# SimGEKI2_Core.net
KiCad netlist of a schematic drawn in EasyEDA Pro
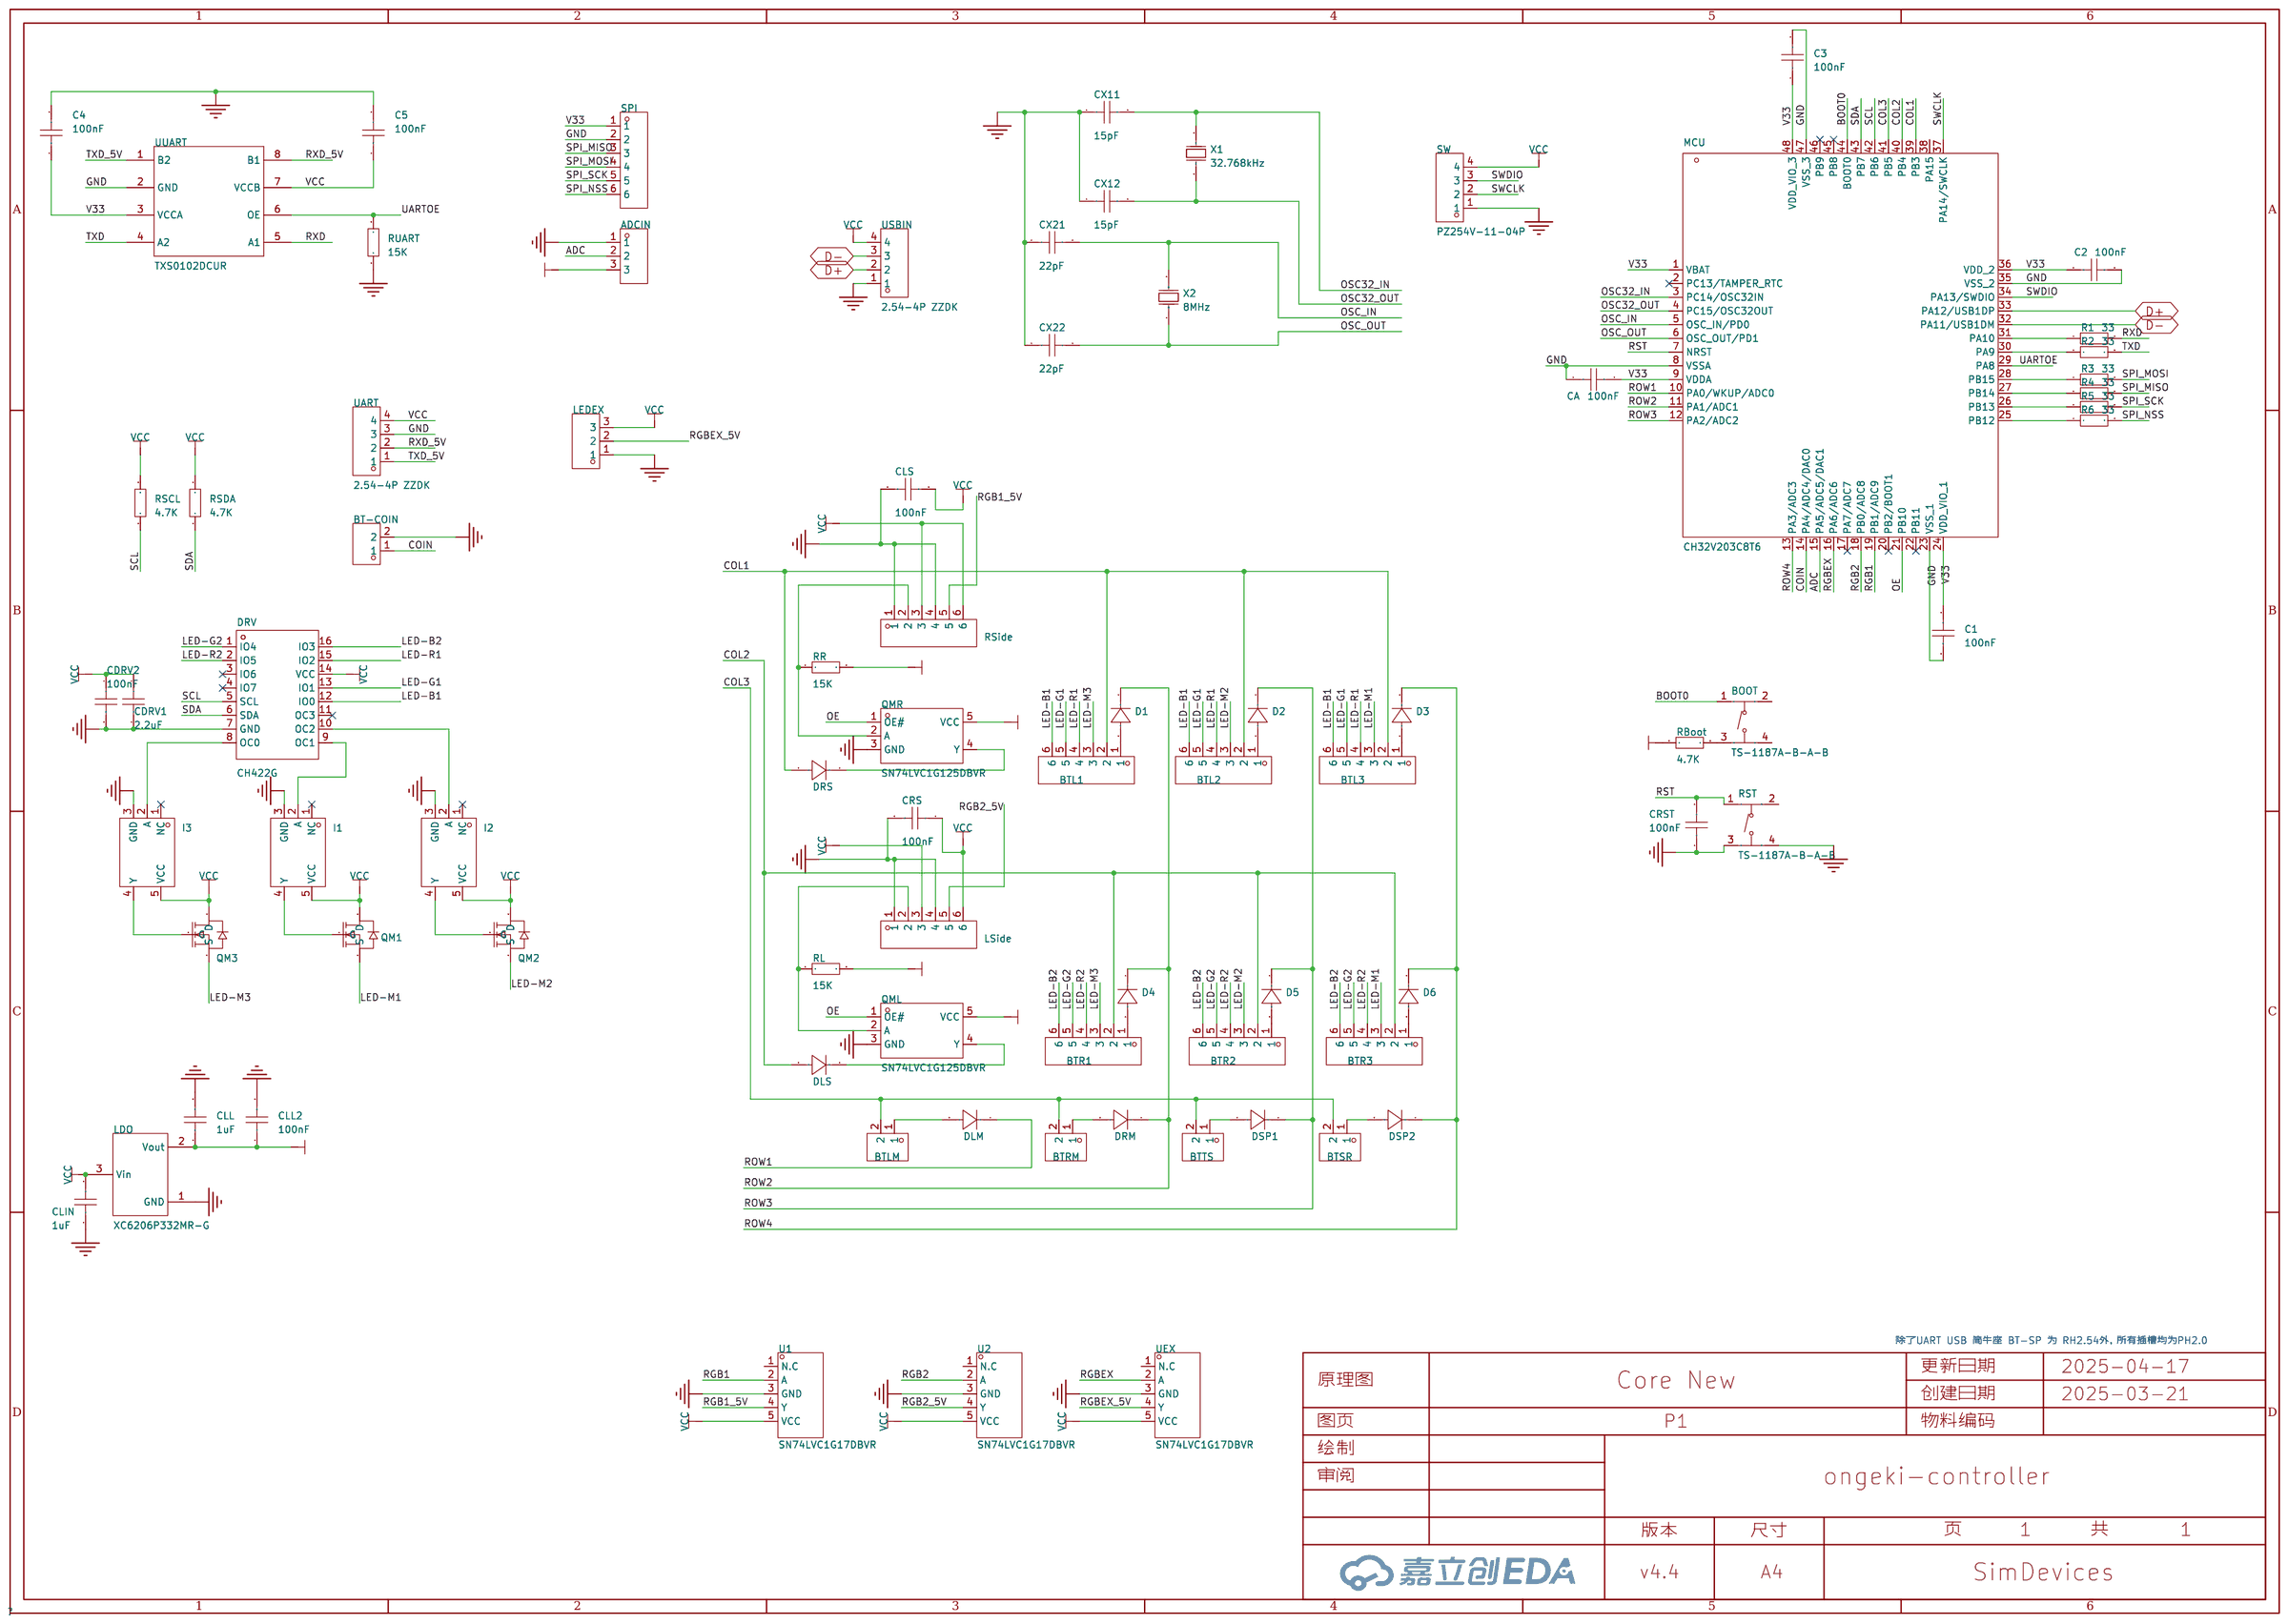
[diagram p0: schematic sheet]

(export (version "E")
  (design (tool "Eeschema 10.0.6"))
  (components
    (comp (ref "ADCIN")
      (value "HDGC2001WV-3P")
      (footprint "easyedapro:CONN-TH_3P-P2.00_HDGC2001WV-3P")
      (fields (field (name "Manufacturer") "HDGC(华德共创)"))
      (libsource (lib "easyedapro") (part "HDGC2001WV-3P"))
    )
    (comp (ref "BOOT")
      (value "TS-1187A-B-A-B")
      (footprint "easyedapro:SW-SMD_4P-L5.1-W5.1-P3.70-LS6.5-TL_H1.5")
      (fields (field (name "Manufacturer") "XKB Connectivity(中国星坤)"))
      (libsource (lib "easyedapro") (part "TS-1187A-B-A-B"))
    )
    (comp (ref "BT-COIN")
      (value "ZX-XH2.54-2PZZ")
      (fields (field (name "Manufacturer") "Megastar(兆星)"))
      (libsource (lib "easyedapro") (part "HDGC2001WV-2P"))
    )
    (comp (ref "BTL1")
      (value "HDGC2001WV-6P")
      (footprint "easyedapro:CONN-TH_6P-P2.00_HDGC2001WV-6P")
      (fields (field (name "Manufacturer") "HDGC(华德共创)"))
      (libsource (lib "easyedapro") (part "HDGC2001WV-6P"))
    )
    (comp (ref "BTL2")
      (value "HDGC2001WV-6P")
      (footprint "easyedapro:CONN-TH_6P-P2.00_HDGC2001WV-6P")
      (fields (field (name "Manufacturer") "HDGC(华德共创)"))
      (libsource (lib "easyedapro") (part "HDGC2001WV-6P"))
    )
    (comp (ref "BTL3")
      (value "HDGC2001WV-6P")
      (footprint "easyedapro:CONN-TH_6P-P2.00_HDGC2001WV-6P")
      (fields (field (name "Manufacturer") "HDGC(华德共创)"))
      (libsource (lib "easyedapro") (part "HDGC2001WV-6P"))
    )
    (comp (ref "BTLM")
      (value "ZX-XH2.54-2PZZ")
      (fields (field (name "Manufacturer") "Megastar(兆星)"))
      (libsource (lib "easyedapro") (part "HDGC2001WV-2P"))
    )
    (comp (ref "BTR1")
      (value "HDGC2001WV-6P")
      (footprint "easyedapro:CONN-TH_6P-P2.00_HDGC2001WV-6P")
      (fields (field (name "Manufacturer") "HDGC(华德共创)"))
      (libsource (lib "easyedapro") (part "HDGC2001WV-6P"))
    )
    (comp (ref "BTR2")
      (value "HDGC2001WV-6P")
      (footprint "easyedapro:CONN-TH_6P-P2.00_HDGC2001WV-6P")
      (fields (field (name "Manufacturer") "HDGC(华德共创)"))
      (libsource (lib "easyedapro") (part "HDGC2001WV-6P"))
    )
    (comp (ref "BTR3")
      (value "HDGC2001WV-6P")
      (footprint "easyedapro:CONN-TH_6P-P2.00_HDGC2001WV-6P")
      (fields (field (name "Manufacturer") "HDGC(华德共创)"))
      (libsource (lib "easyedapro") (part "HDGC2001WV-6P"))
    )
    (comp (ref "BTRM")
      (value "ZX-XH2.54-2PZZ")
      (fields (field (name "Manufacturer") "Megastar(兆星)"))
      (libsource (lib "easyedapro") (part "HDGC2001WV-2P"))
    )
    (comp (ref "BTSR")
      (value "ZX-XH2.54-2PZZ")
      (fields (field (name "Manufacturer") "Megastar(兆星)"))
      (libsource (lib "easyedapro") (part "HDGC2001WV-2P"))
    )
    (comp (ref "BTTS")
      (value "ZX-XH2.54-2PZZ")
      (fields (field (name "Manufacturer") "Megastar(兆星)"))
      (libsource (lib "easyedapro") (part "HDGC2001WV-2P"))
    )
    (comp (ref "C1")
      (value "100nF")
      (footprint "easyedapro:C0603")
      (libsource (lib "easyedapro") (part "CapAcitance"))
    )
    (comp (ref "C2")
      (value "100nF")
      (footprint "easyedapro:C0603")
      (libsource (lib "easyedapro") (part "CapAcitance"))
    )
    (comp (ref "C3")
      (value "100nF")
      (footprint "easyedapro:C0603")
      (libsource (lib "easyedapro") (part "CapAcitance"))
    )
    (comp (ref "C4")
      (value "100nF")
      (footprint "easyedapro:C0603")
      (libsource (lib "easyedapro") (part "CapAcitance"))
    )
    (comp (ref "C5")
      (value "100nF")
      (footprint "easyedapro:C0603")
      (libsource (lib "easyedapro") (part "CapAcitance"))
    )
    (comp (ref "CA")
      (value "100nF")
      (footprint "easyedapro:C0603")
      (libsource (lib "easyedapro") (part "CapAcitance"))
    )
    (comp (ref "CDRV1")
      (value "2.2uF")
      (footprint "easyedapro:C0603")
      (libsource (lib "easyedapro") (part "CapAcitance"))
    )
    (comp (ref "CDRV2")
      (value "100nF")
      (footprint "easyedapro:C0603")
      (libsource (lib "easyedapro") (part "CapAcitance"))
    )
    (comp (ref "CLIN")
      (value "1uF")
      (footprint "easyedapro:C0603")
      (libsource (lib "easyedapro") (part "CapAcitance"))
    )
    (comp (ref "CLL")
      (value "1uF")
      (footprint "easyedapro:C0603")
      (libsource (lib "easyedapro") (part "CapAcitance"))
    )
    (comp (ref "CLL2")
      (value "100nF")
      (footprint "easyedapro:C0603")
      (libsource (lib "easyedapro") (part "CapAcitance"))
    )
    (comp (ref "CLS")
      (value "100nF")
      (footprint "easyedapro:C0603")
      (libsource (lib "easyedapro") (part "CapAcitance"))
    )
    (comp (ref "CRS")
      (value "100nF")
      (footprint "easyedapro:C0603")
      (libsource (lib "easyedapro") (part "CapAcitance"))
    )
    (comp (ref "CRST")
      (value "100nF")
      (footprint "easyedapro:C0603")
      (libsource (lib "easyedapro") (part "CapAcitance"))
    )
    (comp (ref "CX11")
      (value "15pF")
      (footprint "easyedapro:C0603")
      (libsource (lib "easyedapro") (part "CapAcitance"))
    )
    (comp (ref "CX12")
      (value "15pF")
      (footprint "easyedapro:C0603")
      (libsource (lib "easyedapro") (part "CapAcitance"))
    )
    (comp (ref "CX21")
      (value "22pF")
      (footprint "easyedapro:C0603")
      (libsource (lib "easyedapro") (part "CapAcitance"))
    )
    (comp (ref "CX22")
      (value "22pF")
      (footprint "easyedapro:C0603")
      (libsource (lib "easyedapro") (part "CapAcitance"))
    )
    (comp (ref "D1")
      (value "1N4148W")
      (fields (field (name "Manufacturer") "ST(先科)"))
      (libsource (lib "easyedapro") (part "1N4007_C9900004759"))
    )
    (comp (ref "D2")
      (value "1N4148W")
      (fields (field (name "Manufacturer") "ST(先科)"))
      (libsource (lib "easyedapro") (part "1N4007_C9900004759"))
    )
    (comp (ref "D3")
      (value "1N4148W")
      (fields (field (name "Manufacturer") "ST(先科)"))
      (libsource (lib "easyedapro") (part "1N4007_C9900004759"))
    )
    (comp (ref "D4")
      (value "1N4148W")
      (fields (field (name "Manufacturer") "ST(先科)"))
      (libsource (lib "easyedapro") (part "1N4007_C9900004759"))
    )
    (comp (ref "D5")
      (value "1N4148W")
      (fields (field (name "Manufacturer") "ST(先科)"))
      (libsource (lib "easyedapro") (part "1N4007_C9900004759"))
    )
    (comp (ref "D6")
      (value "1N4148W")
      (fields (field (name "Manufacturer") "ST(先科)"))
      (libsource (lib "easyedapro") (part "1N4007_C9900004759"))
    )
    (comp (ref "DLM")
      (value "1N4148W")
      (fields (field (name "Manufacturer") "ST(先科)"))
      (libsource (lib "easyedapro") (part "1N4007_C9900004759"))
    )
    (comp (ref "DLS")
      (value "1N4148W")
      (fields (field (name "Manufacturer") "ST(先科)"))
      (libsource (lib "easyedapro") (part "1N4007_C9900004759"))
    )
    (comp (ref "DRM")
      (value "1N4148W")
      (fields (field (name "Manufacturer") "ST(先科)"))
      (libsource (lib "easyedapro") (part "1N4007_C9900004759"))
    )
    (comp (ref "DRS")
      (value "1N4148W")
      (fields (field (name "Manufacturer") "ST(先科)"))
      (libsource (lib "easyedapro") (part "1N4007_C9900004759"))
    )
    (comp (ref "DRV")
      (value "CH422G")
      (footprint "easyedapro:SOP-16_L10.0-W3.9-P1.27-LS6.0-BL")
      (description "接口:I2C；SPI;I/O数量:8;时钟频率:1MHz;")
      (fields (field (name "Manufacturer") "WCH(南京沁恒)"))
      (libsource (lib "easyedapro") (part "CH422G"))
    )
    (comp (ref "DSP1")
      (value "1N4148W")
      (fields (field (name "Manufacturer") "ST(先科)"))
      (libsource (lib "easyedapro") (part "1N4007_C9900004759"))
    )
    (comp (ref "DSP2")
      (value "1N4148W")
      (fields (field (name "Manufacturer") "ST(先科)"))
      (libsource (lib "easyedapro") (part "1N4007_C9900004759"))
    )
    (comp (ref "I1")
      (value "SN74LVC1G14DBVR")
      (footprint "easyedapro:SOT-23-5_L3.0-W1.7-P0.95-LS2.8-BR")
      (description "逻辑电路的归属系列:-;逻辑类型:-;电路/元件数:-;输入数/每元件位数:-;电源电压:-;静态电流（最大值）:-;")
      (fields (field (name "Manufacturer") "UMW(广东友台半导体)"))
      (libsource (lib "easyedapro") (part "SN74LVC1G14DBVR_C434069"))
    )
    (comp (ref "I2")
      (value "SN74LVC1G14DBVR")
      (footprint "easyedapro:SOT-23-5_L3.0-W1.7-P0.95-LS2.8-BR")
      (description "逻辑电路的归属系列:-;逻辑类型:-;电路/元件数:-;输入数/每元件位数:-;电源电压:-;静态电流（最大值）:-;")
      (fields (field (name "Manufacturer") "UMW(广东友台半导体)"))
      (libsource (lib "easyedapro") (part "SN74LVC1G14DBVR_C434069"))
    )
    (comp (ref "I3")
      (value "SN74LVC1G14DBVR")
      (footprint "easyedapro:SOT-23-5_L3.0-W1.7-P0.95-LS2.8-BR")
      (description "逻辑电路的归属系列:-;逻辑类型:-;电路/元件数:-;输入数/每元件位数:-;电源电压:-;静态电流（最大值）:-;")
      (fields (field (name "Manufacturer") "UMW(广东友台半导体)"))
      (libsource (lib "easyedapro") (part "SN74LVC1G14DBVR_C434069"))
    )
    (comp (ref "LDO")
      (value "XC6206P332MR-G")
      (footprint "easyedapro:SOT-23-3_L2.9-W1.6-P1.90-LS2.8-BR")
      (description "输出类型:固定;最大输入电压:6V;输出电压:3.3V;最大输出电流:200mA;电源纹波抑制比(PSRR):-;输出极性:正极;")
      (fields (field (name "Manufacturer") "TOREX(特瑞仕)"))
      (libsource (lib "easyedapro") (part "XC6206P332MR"))
    )
    (comp (ref "LEDEX")
      (value "HDGC2001WV-3P")
      (footprint "easyedapro:CONN-TH_3P-P2.00_HDGC2001WV-3P")
      (fields (field (name "Manufacturer") "HDGC(华德共创)"))
      (libsource (lib "easyedapro") (part "HDGC2001WV-3P"))
    )
    (comp (ref "LSide")
      (value "HDGC2001WV-6P")
      (footprint "easyedapro:CONN-TH_6P-P2.00_HDGC2001WV-6P")
      (fields (field (name "Manufacturer") "HDGC(华德共创)"))
      (libsource (lib "easyedapro") (part "HDGC2001WV-6P"))
    )
    (comp (ref "MCU")
      (value "CH32V203C8T6")
      (footprint "easyedapro:LQFP-48_L7.0-W7.0-P0.50-LS9.0-BL")
      (description "CPU内核:RISC-V;程序存储容量:64KB;RAM总容量:20KB;GPIO端口数量:-;工作电压范围:-;CPU最大主频:144MHz;程序存储器类型:FLASH;")
      (fields (field (name "Manufacturer") "WCH(南京沁恒)"))
      (libsource (lib "easyedapro") (part "CH32V203C8T6"))
    )
    (comp (ref "QM1") (value "AO3400A") (libsource (lib "easyedapro") (part "N_MOS")))
    (comp (ref "QM2") (value "AO3400A") (libsource (lib "easyedapro") (part "N_MOS")))
    (comp (ref "QM3") (value "AO3400A") (libsource (lib "easyedapro") (part "N_MOS")))
    (comp (ref "QML")
      (value "SN74LVC1G125DBVR")
      (fields (field (name "Manufacturer") "TI(德州仪器)"))
      (libsource (lib "easyedapro") (part "SN74LVC1G240DBVR"))
    )
    (comp (ref "QMR")
      (value "SN74LVC1G125DBVR")
      (fields (field (name "Manufacturer") "TI(德州仪器)"))
      (libsource (lib "easyedapro") (part "SN74LVC1G240DBVR"))
    )
    (comp (ref "R1") (value "33") (footprint "easyedapro:R0402") (libsource (lib "easyedapro") (part "电阻")))
    (comp (ref "R2") (value "33") (footprint "easyedapro:R0402") (libsource (lib "easyedapro") (part "电阻")))
    (comp (ref "R3") (value "33") (footprint "easyedapro:R0402") (libsource (lib "easyedapro") (part "电阻")))
    (comp (ref "R4") (value "33") (footprint "easyedapro:R0402") (libsource (lib "easyedapro") (part "电阻")))
    (comp (ref "R5") (value "33") (footprint "easyedapro:R0402") (libsource (lib "easyedapro") (part "电阻")))
    (comp (ref "R6") (value "33") (footprint "easyedapro:R0402") (libsource (lib "easyedapro") (part "电阻")))
    (comp (ref "RBoot")
      (value "4.7K")
      (footprint "easyedapro:R0603")
      (libsource (lib "easyedapro") (part "电阻"))
    )
    (comp (ref "RL") (value "15K") (footprint "easyedapro:R0603") (libsource (lib "easyedapro") (part "电阻")))
    (comp (ref "RR") (value "15K") (footprint "easyedapro:R0603") (libsource (lib "easyedapro") (part "电阻")))
    (comp (ref "RSCL")
      (value "4.7K")
      (footprint "easyedapro:R0603")
      (libsource (lib "easyedapro") (part "电阻"))
    )
    (comp (ref "RSDA")
      (value "4.7K")
      (footprint "easyedapro:R0603")
      (libsource (lib "easyedapro") (part "电阻"))
    )
    (comp (ref "RSide")
      (value "HDGC2001WV-6P")
      (footprint "easyedapro:CONN-TH_6P-P2.00_HDGC2001WV-6P")
      (fields (field (name "Manufacturer") "HDGC(华德共创)"))
      (libsource (lib "easyedapro") (part "HDGC2001WV-6P"))
    )
    (comp (ref "RST")
      (value "TS-1187A-B-A-B")
      (footprint "easyedapro:SW-SMD_4P-L5.1-W5.1-P3.70-LS6.5-TL_H1.5")
      (fields (field (name "Manufacturer") "XKB Connectivity(中国星坤)"))
      (libsource (lib "easyedapro") (part "TS-1187A-B-A-B"))
    )
    (comp (ref "RUART")
      (value "15K")
      (footprint "easyedapro:R0603")
      (libsource (lib "easyedapro") (part "电阻"))
    )
    (comp (ref "SPI")
      (value "HDGC2001WV-6P")
      (footprint "easyedapro:CONN-TH_6P-P2.00_HDGC2001WV-6P")
      (fields (field (name "Manufacturer") "HDGC(华德共创)"))
      (libsource (lib "easyedapro") (part "HDGC2001WV-6P"))
    )
    (comp (ref "SW")
      (value "PZ254V-11-04P")
      (footprint "easyedapro:HDR-TH_4P-P2.54-V-M")
      (fields (field (name "Manufacturer") "XFCN(兴飞)"))
      (libsource (lib "easyedapro") (part "PZ254V-11-04P_C2691448"))
    )
    (comp (ref "U1")
      (value "SN74LVC1G17DBVR")
      (footprint "easyedapro:SOT-23-5_L3.0-W1.7-P0.95-LS2.8-BR")
      (description "输入类型:施密特触发器;电源电压:1.65V~5.5V;元件数:1;每个元件位数:1;灌电流(IOL):32mA;拉电流(IOH):32mA;")
      (fields (field (name "Manufacturer") "TI(德州仪器)"))
      (libsource (lib "easyedapro") (part "SN74LVC1G17DBVR"))
    )
    (comp (ref "U2")
      (value "SN74LVC1G17DBVR")
      (footprint "easyedapro:SOT-23-5_L3.0-W1.7-P0.95-LS2.8-BR")
      (description "输入类型:施密特触发器;电源电压:1.65V~5.5V;元件数:1;每个元件位数:1;灌电流(IOL):32mA;拉电流(IOH):32mA;")
      (fields (field (name "Manufacturer") "TI(德州仪器)"))
      (libsource (lib "easyedapro") (part "SN74LVC1G17DBVR"))
    )
    (comp (ref "UART")
      (value "2.54-4P ZZDK")
      (footprint "easyedapro:HDR-TH_4P-P2.50-V-F-2")
      (fields (field (name "Manufacturer") "SHOU HAN(首韩)"))
      (libsource (lib "easyedapro") (part "2.54-4P ZZDK"))
    )
    (comp (ref "UEX")
      (value "SN74LVC1G17DBVR")
      (footprint "easyedapro:SOT-23-5_L3.0-W1.7-P0.95-LS2.8-BR")
      (description "输入类型:施密特触发器;电源电压:1.65V~5.5V;元件数:1;每个元件位数:1;灌电流(IOL):32mA;拉电流(IOH):32mA;")
      (fields (field (name "Manufacturer") "TI(德州仪器)"))
      (libsource (lib "easyedapro") (part "SN74LVC1G17DBVR"))
    )
    (comp (ref "USBIN")
      (value "2.54-4P ZZDK")
      (footprint "easyedapro:HDR-TH_4P-P2.50-V-F-2")
      (fields (field (name "Manufacturer") "SHOU HAN(首韩)"))
      (libsource (lib "easyedapro") (part "2.54-4P ZZDK"))
    )
    (comp (ref "UUART")
      (value "TXS0102DCUR")
      (fields (field (name "Manufacturer") "TI(德州仪器)"))
      (libsource (lib "easyedapro") (part "TXB0102DCUR"))
    )
    (comp (ref "X1")
      (value "32.768kHz")
      (footprint "easyedapro:CRYSTAL-SMD_L3.2-W1.5-1")
      (description "晶振类型:贴片晶振;频率:32.768kHz;常温频差:±20ppm;负载电容:12.5pF;频率稳定度:±30ppm;")
      (fields
        (field (name "Manufacturer Part") "XKXGI-SUA-32.768K")
        (field (name "Manufacturer") "YXC(扬兴晶振)")
      )
      (libsource (lib "easyedapro") (part "XKXGI-SUA-32.768K"))
    )
    (comp (ref "X2")
      (value "8MHz")
      (footprint "easyedapro:CRYSTAL-SMD_L5.0-W3.2")
      (description "晶振类型:贴片晶振;频率:8MHz;常温频差:±10ppm;负载电容:20pF;频率稳定度:±20ppm;")
      (fields
        (field (name "Manufacturer Part") "XG1EL89CSI-111YLC-8M")
        (field (name "Manufacturer") "YXC(扬兴晶振)")
      )
      (libsource (lib "easyedapro") (part "XG1EL89CSI-111YLC-8M"))
    )
  )
  (nets
    (net (code "1") (name "/ADC") (class "Default")
      (node (ref "ADCIN") (pin "2") (pinfunction "2_2") (pintype "input"))
      (node (ref "MCU") (pin "15") (pinfunction "PA5/ADC5/DAC1_15") (pintype "unspecified"))
    )
    (net (code "2") (name "/BOOT0") (class "Default")
      (node (ref "BOOT") (pin "1") (pinfunction "A_1") (pintype "unspecified"))
      (node (ref "MCU") (pin "44") (pinfunction "BOOT0_44") (pintype "unspecified"))
    )
    (net (code "3") (name "/COIN") (class "Default")
      (node (ref "BT-COIN") (pin "1") (pinfunction "1_1") (pintype "input"))
      (node (ref "MCU") (pin "14") (pinfunction "PA4/ADC4/DAC0_14") (pintype "unspecified"))
    )
    (net (code "4") (name "/COL1") (class "Default")
      (node (ref "BTL1") (pin "2") (pinfunction "2_2") (pintype "input"))
      (node (ref "BTL2") (pin "2") (pinfunction "2_2") (pintype "input"))
      (node (ref "BTL3") (pin "2") (pinfunction "2_2") (pintype "input"))
      (node (ref "DRS") (pin "2") (pinfunction "A_2") (pintype "input"))
      (node (ref "MCU") (pin "39") (pinfunction "PB3_39") (pintype "unspecified"))
    )
    (net (code "5") (name "/COL2") (class "Default")
      (node (ref "BTR1") (pin "2") (pinfunction "2_2") (pintype "input"))
      (node (ref "BTR2") (pin "2") (pinfunction "2_2") (pintype "input"))
      (node (ref "BTR3") (pin "2") (pinfunction "2_2") (pintype "input"))
      (node (ref "DLS") (pin "2") (pinfunction "A_2") (pintype "input"))
      (node (ref "MCU") (pin "40") (pinfunction "PB4_40") (pintype "unspecified"))
    )
    (net (code "6") (name "/COL3") (class "Default")
      (node (ref "BTLM") (pin "2") (pinfunction "2_2") (pintype "input"))
      (node (ref "BTRM") (pin "2") (pinfunction "2_2") (pintype "input"))
      (node (ref "BTSR") (pin "2") (pinfunction "2_2") (pintype "input"))
      (node (ref "BTTS") (pin "2") (pinfunction "2_2") (pintype "input"))
      (node (ref "MCU") (pin "41") (pinfunction "PB5_41") (pintype "unspecified"))
    )
    (net (code "7") (name "/LED-B1") (class "Default")
      (node (ref "BTL1") (pin "6") (pinfunction "6_6") (pintype "input"))
      (node (ref "BTL2") (pin "6") (pinfunction "6_6") (pintype "input"))
      (node (ref "BTL3") (pin "6") (pinfunction "6_6") (pintype "input"))
      (node (ref "DRV") (pin "12") (pinfunction "IO0_12") (pintype "unspecified"))
    )
    (net (code "8") (name "/LED-B2") (class "Default")
      (node (ref "BTR1") (pin "6") (pinfunction "6_6") (pintype "input"))
      (node (ref "BTR2") (pin "6") (pinfunction "6_6") (pintype "input"))
      (node (ref "BTR3") (pin "6") (pinfunction "6_6") (pintype "input"))
      (node (ref "DRV") (pin "16") (pinfunction "IO3_16") (pintype "unspecified"))
    )
    (net (code "9") (name "/LED-G1") (class "Default")
      (node (ref "BTL1") (pin "5") (pinfunction "5_5") (pintype "input"))
      (node (ref "BTL2") (pin "5") (pinfunction "5_5") (pintype "input"))
      (node (ref "BTL3") (pin "5") (pinfunction "5_5") (pintype "input"))
      (node (ref "DRV") (pin "13") (pinfunction "IO1_13") (pintype "unspecified"))
    )
    (net (code "10") (name "/LED-G2") (class "Default")
      (node (ref "BTR1") (pin "5") (pinfunction "5_5") (pintype "input"))
      (node (ref "BTR2") (pin "5") (pinfunction "5_5") (pintype "input"))
      (node (ref "BTR3") (pin "5") (pinfunction "5_5") (pintype "input"))
      (node (ref "DRV") (pin "1") (pinfunction "IO4_1") (pintype "unspecified"))
    )
    (net (code "11") (name "/LED-M1") (class "Default")
      (node (ref "BTL3") (pin "3") (pinfunction "3_3") (pintype "input"))
      (node (ref "BTR3") (pin "3") (pinfunction "3_3") (pintype "input"))
      (node (ref "QM1") (pin "2") (pinfunction "S_2") (pintype "input"))
    )
    (net (code "12") (name "/LED-M2") (class "Default")
      (node (ref "BTL2") (pin "3") (pinfunction "3_3") (pintype "input"))
      (node (ref "BTR2") (pin "3") (pinfunction "3_3") (pintype "input"))
      (node (ref "QM2") (pin "2") (pinfunction "S_2") (pintype "input"))
    )
    (net (code "13") (name "/LED-M3") (class "Default")
      (node (ref "BTL1") (pin "3") (pinfunction "3_3") (pintype "input"))
      (node (ref "BTR1") (pin "3") (pinfunction "3_3") (pintype "input"))
      (node (ref "QM3") (pin "2") (pinfunction "S_2") (pintype "input"))
    )
    (net (code "14") (name "/LED-R1") (class "Default")
      (node (ref "BTL1") (pin "4") (pinfunction "4_4") (pintype "input"))
      (node (ref "BTL2") (pin "4") (pinfunction "4_4") (pintype "input"))
      (node (ref "BTL3") (pin "4") (pinfunction "4_4") (pintype "input"))
      (node (ref "DRV") (pin "15") (pinfunction "IO2_15") (pintype "unspecified"))
    )
    (net (code "15") (name "/LED-R2") (class "Default")
      (node (ref "BTR1") (pin "4") (pinfunction "4_4") (pintype "input"))
      (node (ref "BTR2") (pin "4") (pinfunction "4_4") (pintype "input"))
      (node (ref "BTR3") (pin "4") (pinfunction "4_4") (pintype "input"))
      (node (ref "DRV") (pin "2") (pinfunction "IO5_2") (pintype "unspecified"))
    )
    (net (code "16") (name "/OE") (class "Default")
      (node (ref "MCU") (pin "21") (pinfunction "PB10_21") (pintype "unspecified"))
      (node (ref "QML") (pin "1") (pinfunction "OE#_1") (pintype "input"))
      (node (ref "QMR") (pin "1") (pinfunction "OE#_1") (pintype "input"))
    )
    (net (code "17") (name "/OSC32_IN") (class "Default")
      (node (ref "CX11") (pin "2") (pinfunction "2_2") (pintype "input"))
      (node (ref "MCU") (pin "3") (pinfunction "PC14/OSC32IN_3") (pintype "unspecified"))
      (node (ref "X1") (pin "2") (pinfunction "OSC2_2") (pintype "input"))
    )
    (net (code "18") (name "/OSC32_OUT") (class "Default")
      (node (ref "CX12") (pin "2") (pinfunction "2_2") (pintype "input"))
      (node (ref "MCU") (pin "4") (pinfunction "PC15/OSC32OUT_4") (pintype "unspecified"))
      (node (ref "X1") (pin "1") (pinfunction "OSC1_1") (pintype "input"))
    )
    (net (code "19") (name "/OSC_IN") (class "Default")
      (node (ref "CX21") (pin "2") (pinfunction "2_2") (pintype "input"))
      (node (ref "MCU") (pin "5") (pinfunction "OSC_IN/PD0_5") (pintype "unspecified"))
      (node (ref "X2") (pin "2") (pinfunction "OSC2_2") (pintype "input"))
    )
    (net (code "20") (name "/OSC_OUT") (class "Default")
      (node (ref "CX22") (pin "2") (pinfunction "2_2") (pintype "input"))
      (node (ref "MCU") (pin "6") (pinfunction "OSC_OUT/PD1_6") (pintype "unspecified"))
      (node (ref "X2") (pin "1") (pinfunction "OSC1_1") (pintype "input"))
    )
    (net (code "21") (name "/RGB1") (class "Default")
      (node (ref "MCU") (pin "19") (pinfunction "PB1/ADC9_19") (pintype "unspecified"))
      (node (ref "U1") (pin "2") (pinfunction "A_2") (pintype "input"))
    )
    (net (code "22") (name "/RGB1_5V") (class "Default")
      (node (ref "RSide") (pin "5") (pinfunction "5_5") (pintype "input"))
      (node (ref "U1") (pin "4") (pinfunction "Y_4") (pintype "input"))
    )
    (net (code "23") (name "/RGB2") (class "Default")
      (node (ref "MCU") (pin "18") (pinfunction "PB0/ADC8_18") (pintype "unspecified"))
      (node (ref "U2") (pin "2") (pinfunction "A_2") (pintype "input"))
    )
    (net (code "24") (name "/RGB2_5V") (class "Default")
      (node (ref "LSide") (pin "5") (pinfunction "5_5") (pintype "input"))
      (node (ref "U2") (pin "4") (pinfunction "Y_4") (pintype "input"))
    )
    (net (code "25") (name "/RGBEX") (class "Default")
      (node (ref "MCU") (pin "16") (pinfunction "PA6/ADC6_16") (pintype "unspecified"))
      (node (ref "UEX") (pin "2") (pinfunction "A_2") (pintype "input"))
    )
    (net (code "26") (name "/RGBEX_5V") (class "Default")
      (node (ref "LEDEX") (pin "2") (pinfunction "2_2") (pintype "input"))
      (node (ref "UEX") (pin "4") (pinfunction "Y_4") (pintype "input"))
    )
    (net (code "27") (name "/ROW1") (class "Default")
      (node (ref "DLM") (pin "1") (pinfunction "K_1") (pintype "input"))
      (node (ref "MCU") (pin "10") (pinfunction "PA0/WKUP/ADC0_10") (pintype "unspecified"))
    )
    (net (code "28") (name "/ROW2") (class "Default")
      (node (ref "D1") (pin "1") (pinfunction "K_1") (pintype "input"))
      (node (ref "D4") (pin "1") (pinfunction "K_1") (pintype "input"))
      (node (ref "DRM") (pin "1") (pinfunction "K_1") (pintype "input"))
      (node (ref "MCU") (pin "11") (pinfunction "PA1/ADC1_11") (pintype "unspecified"))
    )
    (net (code "29") (name "/ROW3") (class "Default")
      (node (ref "D2") (pin "1") (pinfunction "K_1") (pintype "input"))
      (node (ref "D5") (pin "1") (pinfunction "K_1") (pintype "input"))
      (node (ref "DSP1") (pin "1") (pinfunction "K_1") (pintype "input"))
      (node (ref "MCU") (pin "12") (pinfunction "PA2/ADC2_12") (pintype "unspecified"))
    )
    (net (code "30") (name "/ROW4") (class "Default")
      (node (ref "D3") (pin "1") (pinfunction "K_1") (pintype "input"))
      (node (ref "D6") (pin "1") (pinfunction "K_1") (pintype "input"))
      (node (ref "DSP2") (pin "1") (pinfunction "K_1") (pintype "input"))
      (node (ref "MCU") (pin "13") (pinfunction "PA3/ADC3_13") (pintype "unspecified"))
    )
    (net (code "31") (name "/RST") (class "Default")
      (node (ref "CRST") (pin "2") (pinfunction "2_2") (pintype "input"))
      (node (ref "MCU") (pin "7") (pinfunction "NRST_7") (pintype "unspecified"))
      (node (ref "RST") (pin "1") (pinfunction "A_1") (pintype "unspecified"))
    )
    (net (code "32") (name "/RXD") (class "Default")
      (node (ref "R1") (pin "2") (pinfunction "2_2") (pintype "input"))
      (node (ref "UUART") (pin "5") (pinfunction "A1_5") (pintype "unspecified"))
    )
    (net (code "33") (name "/RXD_5V") (class "Default")
      (node (ref "UART") (pin "2") (pinfunction "2_2") (pintype "unspecified"))
      (node (ref "UUART") (pin "8") (pinfunction "B1_8") (pintype "unspecified"))
    )
    (net (code "34") (name "/SCL") (class "Default")
      (node (ref "DRV") (pin "5") (pinfunction "SCL_5") (pintype "unspecified"))
      (node (ref "MCU") (pin "42") (pinfunction "PB6_42") (pintype "unspecified"))
      (node (ref "RSCL") (pin "1") (pinfunction "1_1") (pintype "input"))
    )
    (net (code "35") (name "/SDA") (class "Default")
      (node (ref "DRV") (pin "6") (pinfunction "SDA_6") (pintype "unspecified"))
      (node (ref "MCU") (pin "43") (pinfunction "PB7_43") (pintype "unspecified"))
      (node (ref "RSDA") (pin "1") (pinfunction "1_1") (pintype "input"))
    )
    (net (code "36") (name "/SPI_MISO") (class "Default")
      (node (ref "R4") (pin "2") (pinfunction "2_2") (pintype "input"))
      (node (ref "SPI") (pin "3") (pinfunction "3_3") (pintype "input"))
    )
    (net (code "37") (name "/SPI_MOSI") (class "Default")
      (node (ref "R3") (pin "2") (pinfunction "2_2") (pintype "input"))
      (node (ref "SPI") (pin "4") (pinfunction "4_4") (pintype "input"))
    )
    (net (code "38") (name "/SPI_NSS") (class "Default")
      (node (ref "R6") (pin "2") (pinfunction "2_2") (pintype "input"))
      (node (ref "SPI") (pin "6") (pinfunction "6_6") (pintype "input"))
    )
    (net (code "39") (name "/SPI_SCK") (class "Default")
      (node (ref "R5") (pin "2") (pinfunction "2_2") (pintype "input"))
      (node (ref "SPI") (pin "5") (pinfunction "5_5") (pintype "input"))
    )
    (net (code "40") (name "/SWCLK") (class "Default")
      (node (ref "MCU") (pin "37") (pinfunction "PA14/SWCLK_37") (pintype "unspecified"))
      (node (ref "SW") (pin "2") (pinfunction "2_2") (pintype "unspecified"))
    )
    (net (code "41") (name "/SWDIO") (class "Default")
      (node (ref "MCU") (pin "34") (pinfunction "PA13/SWDIO_34") (pintype "unspecified"))
      (node (ref "SW") (pin "3") (pinfunction "3_3") (pintype "unspecified"))
    )
    (net (code "42") (name "/TXD") (class "Default")
      (node (ref "R2") (pin "2") (pinfunction "2_2") (pintype "input"))
      (node (ref "UUART") (pin "4") (pinfunction "A2_4") (pintype "unspecified"))
    )
    (net (code "43") (name "/TXD_5V") (class "Default")
      (node (ref "UART") (pin "1") (pinfunction "1_1") (pintype "unspecified"))
      (node (ref "UUART") (pin "1") (pinfunction "B2_1") (pintype "unspecified"))
    )
    (net (code "44") (name "/UARTOE") (class "Default")
      (node (ref "MCU") (pin "29") (pinfunction "PA8_29") (pintype "unspecified"))
      (node (ref "RUART") (pin "2") (pinfunction "2_2") (pintype "input"))
      (node (ref "UUART") (pin "6") (pinfunction "OE_6") (pintype "unspecified"))
    )
    (net (code "45") (name "D+") (class "Default")
      (node (ref "MCU") (pin "33") (pinfunction "PA12/USB1DP_33") (pintype "unspecified"))
      (node (ref "USBIN") (pin "2") (pinfunction "2_2") (pintype "unspecified"))
    )
    (net (code "46") (name "D-") (class "Default")
      (node (ref "MCU") (pin "32") (pinfunction "PA11/USB1DM_32") (pintype "unspecified"))
      (node (ref "USBIN") (pin "3") (pinfunction "3_3") (pintype "unspecified"))
    )
    (net (code "47") (name "GND") (class "Default")
      (node (ref "ADCIN") (pin "1") (pinfunction "1_1") (pintype "input"))
      (node (ref "BT-COIN") (pin "2") (pinfunction "2_2") (pintype "input"))
      (node (ref "C1") (pin "2") (pinfunction "2_2") (pintype "input"))
      (node (ref "C2") (pin "2") (pinfunction "2_2") (pintype "input"))
      (node (ref "C3") (pin "2") (pinfunction "2_2") (pintype "input"))
      (node (ref "C4") (pin "2") (pinfunction "2_2") (pintype "input"))
      (node (ref "C5") (pin "2") (pinfunction "2_2") (pintype "input"))
      (node (ref "CA") (pin "1") (pinfunction "1_1") (pintype "input"))
      (node (ref "CDRV1") (pin "2") (pinfunction "2_2") (pintype "input"))
      (node (ref "CDRV2") (pin "2") (pinfunction "2_2") (pintype "input"))
      (node (ref "CLIN") (pin "1") (pinfunction "1_1") (pintype "input"))
      (node (ref "CLL") (pin "2") (pinfunction "2_2") (pintype "input"))
      (node (ref "CLL2") (pin "2") (pinfunction "2_2") (pintype "input"))
      (node (ref "CLS") (pin "2") (pinfunction "2_2") (pintype "input"))
      (node (ref "CRS") (pin "2") (pinfunction "2_2") (pintype "input"))
      (node (ref "CRST") (pin "1") (pinfunction "1_1") (pintype "input"))
      (node (ref "CX11") (pin "1") (pinfunction "1_1") (pintype "input"))
      (node (ref "CX12") (pin "1") (pinfunction "1_1") (pintype "input"))
      (node (ref "CX21") (pin "1") (pinfunction "1_1") (pintype "input"))
      (node (ref "CX22") (pin "1") (pinfunction "1_1") (pintype "input"))
      (node (ref "DRV") (pin "7") (pinfunction "GND_7") (pintype "unspecified"))
      (node (ref "I1") (pin "3") (pinfunction "GND_3") (pintype "input"))
      (node (ref "I2") (pin "3") (pinfunction "GND_3") (pintype "input"))
      (node (ref "I3") (pin "3") (pinfunction "GND_3") (pintype "input"))
      (node (ref "LDO") (pin "1") (pinfunction "GND_1") (pintype "unspecified"))
      (node (ref "LEDEX") (pin "1") (pinfunction "1_1") (pintype "input"))
      (node (ref "LSide") (pin "1") (pinfunction "1_1") (pintype "input"))
      (node (ref "LSide") (pin "4") (pinfunction "4_4") (pintype "input"))
      (node (ref "MCU") (pin "23") (pinfunction "VSS_1_23") (pintype "unspecified"))
      (node (ref "MCU") (pin "35") (pinfunction "VSS_2_35") (pintype "unspecified"))
      (node (ref "MCU") (pin "47") (pinfunction "VSS_3_47") (pintype "unspecified"))
      (node (ref "MCU") (pin "8") (pinfunction "VSSA_8") (pintype "unspecified"))
      (node (ref "QML") (pin "3") (pinfunction "GND_3") (pintype "input"))
      (node (ref "QMR") (pin "3") (pinfunction "GND_3") (pintype "input"))
      (node (ref "RST") (pin "3") (pinfunction "C_3") (pintype "unspecified"))
      (node (ref "RST") (pin "4") (pinfunction "D_4") (pintype "unspecified"))
      (node (ref "RSide") (pin "1") (pinfunction "1_1") (pintype "input"))
      (node (ref "RSide") (pin "4") (pinfunction "4_4") (pintype "input"))
      (node (ref "RUART") (pin "1") (pinfunction "1_1") (pintype "input"))
      (node (ref "SPI") (pin "2") (pinfunction "2_2") (pintype "input"))
      (node (ref "SW") (pin "1") (pinfunction "1_1") (pintype "unspecified"))
      (node (ref "U1") (pin "3") (pinfunction "GND_3") (pintype "input"))
      (node (ref "U2") (pin "3") (pinfunction "GND_3") (pintype "input"))
      (node (ref "UART") (pin "3") (pinfunction "3_3") (pintype "unspecified"))
      (node (ref "UEX") (pin "3") (pinfunction "GND_3") (pintype "input"))
      (node (ref "USBIN") (pin "1") (pinfunction "1_1") (pintype "unspecified"))
      (node (ref "UUART") (pin "2") (pinfunction "GND_2") (pintype "input"))
    )
    (net (code "48") (name "Net-(BOOT-C)") (class "Default")
      (node (ref "BOOT") (pin "3") (pinfunction "C_3") (pintype "unspecified"))
      (node (ref "RBoot") (pin "2") (pinfunction "2_2") (pintype "input"))
    )
    (net (code "49") (name "Net-(D1-A)") (class "Default")
      (node (ref "BTL1") (pin "1") (pinfunction "1_1") (pintype "input"))
      (node (ref "D1") (pin "2") (pinfunction "A_2") (pintype "input"))
    )
    (net (code "50") (name "Net-(D2-A)") (class "Default")
      (node (ref "BTL2") (pin "1") (pinfunction "1_1") (pintype "input"))
      (node (ref "D2") (pin "2") (pinfunction "A_2") (pintype "input"))
    )
    (net (code "51") (name "Net-(D3-A)") (class "Default")
      (node (ref "BTL3") (pin "1") (pinfunction "1_1") (pintype "input"))
      (node (ref "D3") (pin "2") (pinfunction "A_2") (pintype "input"))
    )
    (net (code "52") (name "Net-(D4-A)") (class "Default")
      (node (ref "BTR1") (pin "1") (pinfunction "1_1") (pintype "input"))
      (node (ref "D4") (pin "2") (pinfunction "A_2") (pintype "input"))
    )
    (net (code "53") (name "Net-(D5-A)") (class "Default")
      (node (ref "BTR2") (pin "1") (pinfunction "1_1") (pintype "input"))
      (node (ref "D5") (pin "2") (pinfunction "A_2") (pintype "input"))
    )
    (net (code "54") (name "Net-(D6-A)") (class "Default")
      (node (ref "BTR3") (pin "1") (pinfunction "1_1") (pintype "input"))
      (node (ref "D6") (pin "2") (pinfunction "A_2") (pintype "input"))
    )
    (net (code "55") (name "Net-(DLM-A)") (class "Default")
      (node (ref "BTLM") (pin "1") (pinfunction "1_1") (pintype "input"))
      (node (ref "DLM") (pin "2") (pinfunction "A_2") (pintype "input"))
    )
    (net (code "56") (name "Net-(DLS-K)") (class "Default")
      (node (ref "DLS") (pin "1") (pinfunction "K_1") (pintype "input"))
      (node (ref "QML") (pin "4") (pinfunction "Y_4") (pintype "input"))
    )
    (net (code "57") (name "Net-(DRM-A)") (class "Default")
      (node (ref "BTRM") (pin "1") (pinfunction "1_1") (pintype "input"))
      (node (ref "DRM") (pin "2") (pinfunction "A_2") (pintype "input"))
    )
    (net (code "58") (name "Net-(DRS-K)") (class "Default")
      (node (ref "DRS") (pin "1") (pinfunction "K_1") (pintype "input"))
      (node (ref "QMR") (pin "4") (pinfunction "Y_4") (pintype "input"))
    )
    (net (code "59") (name "Net-(DRV-OC0)") (class "Default")
      (node (ref "DRV") (pin "8") (pinfunction "OC0_8") (pintype "unspecified"))
      (node (ref "I3") (pin "2") (pinfunction "A_2") (pintype "input"))
    )
    (net (code "60") (name "Net-(DRV-OC1)") (class "Default")
      (node (ref "DRV") (pin "9") (pinfunction "OC1_9") (pintype "unspecified"))
      (node (ref "I1") (pin "2") (pinfunction "A_2") (pintype "input"))
    )
    (net (code "61") (name "Net-(DRV-OC2)") (class "Default")
      (node (ref "DRV") (pin "10") (pinfunction "OC2_10") (pintype "unspecified"))
      (node (ref "I2") (pin "2") (pinfunction "A_2") (pintype "input"))
    )
    (net (code "62") (name "Net-(DSP1-A)") (class "Default")
      (node (ref "BTTS") (pin "1") (pinfunction "1_1") (pintype "input"))
      (node (ref "DSP1") (pin "2") (pinfunction "A_2") (pintype "input"))
    )
    (net (code "63") (name "Net-(DSP2-A)") (class "Default")
      (node (ref "BTSR") (pin "1") (pinfunction "1_1") (pintype "input"))
      (node (ref "DSP2") (pin "2") (pinfunction "A_2") (pintype "input"))
    )
    (net (code "64") (name "Net-(I1-Y)") (class "Default")
      (node (ref "I1") (pin "4") (pinfunction "Y_4") (pintype "input"))
      (node (ref "QM1") (pin "1") (pinfunction "G_1") (pintype "input"))
    )
    (net (code "65") (name "Net-(I2-Y)") (class "Default")
      (node (ref "I2") (pin "4") (pinfunction "Y_4") (pintype "input"))
      (node (ref "QM2") (pin "1") (pinfunction "G_1") (pintype "input"))
    )
    (net (code "66") (name "Net-(I3-Y)") (class "Default")
      (node (ref "I3") (pin "4") (pinfunction "Y_4") (pintype "input"))
      (node (ref "QM3") (pin "1") (pinfunction "G_1") (pintype "input"))
    )
    (net (code "67") (name "Net-(MCU-PA9)") (class "Default")
      (node (ref "MCU") (pin "30") (pinfunction "PA9_30") (pintype "unspecified"))
      (node (ref "R2") (pin "1") (pinfunction "1_1") (pintype "input"))
    )
    (net (code "68") (name "Net-(MCU-PA10)") (class "Default")
      (node (ref "MCU") (pin "31") (pinfunction "PA10_31") (pintype "unspecified"))
      (node (ref "R1") (pin "1") (pinfunction "1_1") (pintype "input"))
    )
    (net (code "69") (name "Net-(MCU-PB12)") (class "Default")
      (node (ref "MCU") (pin "25") (pinfunction "PB12_25") (pintype "unspecified"))
      (node (ref "R6") (pin "1") (pinfunction "1_1") (pintype "input"))
    )
    (net (code "70") (name "Net-(MCU-PB13)") (class "Default")
      (node (ref "MCU") (pin "26") (pinfunction "PB13_26") (pintype "unspecified"))
      (node (ref "R5") (pin "1") (pinfunction "1_1") (pintype "input"))
    )
    (net (code "71") (name "Net-(MCU-PB14)") (class "Default")
      (node (ref "MCU") (pin "27") (pinfunction "PB14_27") (pintype "unspecified"))
      (node (ref "R4") (pin "1") (pinfunction "1_1") (pintype "input"))
    )
    (net (code "72") (name "Net-(MCU-PB15)") (class "Default")
      (node (ref "MCU") (pin "28") (pinfunction "PB15_28") (pintype "unspecified"))
      (node (ref "R3") (pin "1") (pinfunction "1_1") (pintype "input"))
    )
    (net (code "73") (name "Net-(QML-A)") (class "Default")
      (node (ref "LSide") (pin "2") (pinfunction "2_2") (pintype "input"))
      (node (ref "QML") (pin "2") (pinfunction "A_2") (pintype "input"))
      (node (ref "RL") (pin "1") (pinfunction "1_1") (pintype "input"))
    )
    (net (code "74") (name "Net-(QMR-A)") (class "Default")
      (node (ref "QMR") (pin "2") (pinfunction "A_2") (pintype "input"))
      (node (ref "RR") (pin "1") (pinfunction "1_1") (pintype "input"))
      (node (ref "RSide") (pin "2") (pinfunction "2_2") (pintype "input"))
    )
    (net (code "75") (name "V33") (class "Default")
      (node (ref "ADCIN") (pin "3") (pinfunction "3_3") (pintype "input"))
      (node (ref "C1") (pin "1") (pinfunction "1_1") (pintype "input"))
      (node (ref "C2") (pin "1") (pinfunction "1_1") (pintype "input"))
      (node (ref "C3") (pin "1") (pinfunction "1_1") (pintype "input"))
      (node (ref "C4") (pin "1") (pinfunction "1_1") (pintype "input"))
      (node (ref "CA") (pin "2") (pinfunction "2_2") (pintype "input"))
      (node (ref "CLL") (pin "1") (pinfunction "1_1") (pintype "input"))
      (node (ref "CLL2") (pin "1") (pinfunction "1_1") (pintype "input"))
      (node (ref "LDO") (pin "2") (pinfunction "Vout_2") (pintype "unspecified"))
      (node (ref "MCU") (pin "1") (pinfunction "VBAT_1") (pintype "unspecified"))
      (node (ref "MCU") (pin "24") (pinfunction "VDD_VIO_1_24") (pintype "unspecified"))
      (node (ref "MCU") (pin "36") (pinfunction "VDD_2_36") (pintype "unspecified"))
      (node (ref "MCU") (pin "48") (pinfunction "VDD_VIO_3_48") (pintype "unspecified"))
      (node (ref "MCU") (pin "9") (pinfunction "VDDA_9") (pintype "unspecified"))
      (node (ref "QML") (pin "5") (pinfunction "VCC_5") (pintype "input"))
      (node (ref "QMR") (pin "5") (pinfunction "VCC_5") (pintype "input"))
      (node (ref "RBoot") (pin "1") (pinfunction "1_1") (pintype "input"))
      (node (ref "RL") (pin "2") (pinfunction "2_2") (pintype "input"))
      (node (ref "RR") (pin "2") (pinfunction "2_2") (pintype "input"))
      (node (ref "SPI") (pin "1") (pinfunction "1_1") (pintype "input"))
      (node (ref "UUART") (pin "3") (pinfunction "VCCA_3") (pintype "input"))
    )
    (net (code "76") (name "VCC") (class "Default")
      (node (ref "C5") (pin "1") (pinfunction "1_1") (pintype "input"))
      (node (ref "CDRV1") (pin "1") (pinfunction "1_1") (pintype "input"))
      (node (ref "CDRV2") (pin "1") (pinfunction "1_1") (pintype "input"))
      (node (ref "CLIN") (pin "2") (pinfunction "2_2") (pintype "input"))
      (node (ref "CLS") (pin "1") (pinfunction "1_1") (pintype "input"))
      (node (ref "CRS") (pin "1") (pinfunction "1_1") (pintype "input"))
      (node (ref "DRV") (pin "14") (pinfunction "VCC_14") (pintype "unspecified"))
      (node (ref "I1") (pin "5") (pinfunction "VCC_5") (pintype "input"))
      (node (ref "I2") (pin "5") (pinfunction "VCC_5") (pintype "input"))
      (node (ref "I3") (pin "5") (pinfunction "VCC_5") (pintype "input"))
      (node (ref "LDO") (pin "3") (pinfunction "Vin_3") (pintype "unspecified"))
      (node (ref "LEDEX") (pin "3") (pinfunction "3_3") (pintype "input"))
      (node (ref "LSide") (pin "3") (pinfunction "3_3") (pintype "input"))
      (node (ref "LSide") (pin "6") (pinfunction "6_6") (pintype "input"))
      (node (ref "QM1") (pin "3") (pinfunction "D_3") (pintype "input"))
      (node (ref "QM2") (pin "3") (pinfunction "D_3") (pintype "input"))
      (node (ref "QM3") (pin "3") (pinfunction "D_3") (pintype "input"))
      (node (ref "RSCL") (pin "2") (pinfunction "2_2") (pintype "input"))
      (node (ref "RSDA") (pin "2") (pinfunction "2_2") (pintype "input"))
      (node (ref "RSide") (pin "3") (pinfunction "3_3") (pintype "input"))
      (node (ref "RSide") (pin "6") (pinfunction "6_6") (pintype "input"))
      (node (ref "SW") (pin "4") (pinfunction "4_4") (pintype "unspecified"))
      (node (ref "U1") (pin "5") (pinfunction "VCC_5") (pintype "input"))
      (node (ref "U2") (pin "5") (pinfunction "VCC_5") (pintype "input"))
      (node (ref "UART") (pin "4") (pinfunction "4_4") (pintype "unspecified"))
      (node (ref "UEX") (pin "5") (pinfunction "VCC_5") (pintype "input"))
      (node (ref "USBIN") (pin "4") (pinfunction "4_4") (pintype "unspecified"))
      (node (ref "UUART") (pin "7") (pinfunction "VCCB_7") (pintype "unspecified"))
    )
    (net (code "77") (name "unconnected-(BOOT-B-Pad2)") (class "Default")
      (node (ref "BOOT") (pin "2") (pinfunction "B_2") (pintype "unspecified"))
    )
    (net (code "78") (name "unconnected-(BOOT-D-Pad4)") (class "Default")
      (node (ref "BOOT") (pin "4") (pinfunction "D_4") (pintype "unspecified"))
    )
    (net (code "79") (name "unconnected-(DRV-IO6-Pad3)") (class "Default")
      (node (ref "DRV") (pin "3") (pinfunction "IO6_3") (pintype "unspecified+no_connect"))
    )
    (net (code "80") (name "unconnected-(DRV-IO7-Pad4)") (class "Default")
      (node (ref "DRV") (pin "4") (pinfunction "IO7_4") (pintype "unspecified+no_connect"))
    )
    (net (code "81") (name "unconnected-(DRV-OC3-Pad11)") (class "Default")
      (node (ref "DRV") (pin "11") (pinfunction "OC3_11") (pintype "unspecified+no_connect"))
    )
    (net (code "82") (name "unconnected-(I1-NC-Pad1)") (class "Default")
      (node (ref "I1") (pin "1") (pinfunction "NC_1") (pintype "input+no_connect"))
    )
    (net (code "83") (name "unconnected-(I2-NC-Pad1)") (class "Default")
      (node (ref "I2") (pin "1") (pinfunction "NC_1") (pintype "input+no_connect"))
    )
    (net (code "84") (name "unconnected-(I3-NC-Pad1)") (class "Default")
      (node (ref "I3") (pin "1") (pinfunction "NC_1") (pintype "input+no_connect"))
    )
    (net (code "85") (name "unconnected-(MCU-PA7{slash}ADC7-Pad17)") (class "Default")
      (node (ref "MCU") (pin "17") (pinfunction "PA7/ADC7_17") (pintype "unspecified+no_connect"))
    )
    (net (code "86") (name "unconnected-(MCU-PA15-Pad38)") (class "Default")
      (node (ref "MCU") (pin "38") (pinfunction "PA15_38") (pintype "unspecified"))
    )
    (net (code "87") (name "unconnected-(MCU-PB2{slash}BOOT1-Pad20)") (class "Default")
      (node (ref "MCU") (pin "20") (pinfunction "PB2/BOOT1_20") (pintype "unspecified+no_connect"))
    )
    (net (code "88") (name "unconnected-(MCU-PB8-Pad45)") (class "Default")
      (node (ref "MCU") (pin "45") (pinfunction "PB8_45") (pintype "unspecified+no_connect"))
    )
    (net (code "89") (name "unconnected-(MCU-PB9-Pad46)") (class "Default")
      (node (ref "MCU") (pin "46") (pinfunction "PB9_46") (pintype "unspecified+no_connect"))
    )
    (net (code "90") (name "unconnected-(MCU-PB11-Pad22)") (class "Default")
      (node (ref "MCU") (pin "22") (pinfunction "PB11_22") (pintype "unspecified+no_connect"))
    )
    (net (code "91") (name "unconnected-(MCU-PC13{slash}TAMPER_RTC-Pad2)") (class "Default")
      (node (ref "MCU") (pin "2") (pinfunction "PC13/TAMPER_RTC_2") (pintype "unspecified+no_connect"))
    )
    (net (code "92") (name "unconnected-(RST-B-Pad2)") (class "Default")
      (node (ref "RST") (pin "2") (pinfunction "B_2") (pintype "unspecified"))
    )
    (net (code "93") (name "unconnected-(U1-N.C-Pad1)") (class "Default")
      (node (ref "U1") (pin "1") (pinfunction "N.C_1") (pintype "input"))
    )
    (net (code "94") (name "unconnected-(U2-N.C-Pad1)") (class "Default")
      (node (ref "U2") (pin "1") (pinfunction "N.C_1") (pintype "input"))
    )
    (net (code "95") (name "unconnected-(UEX-N.C-Pad1)") (class "Default")
      (node (ref "UEX") (pin "1") (pinfunction "N.C_1") (pintype "input"))
    )
  )
)
